# MB1296-USB_Antenna.net
KiCad netlist of a schematic drawn in Altium Designer
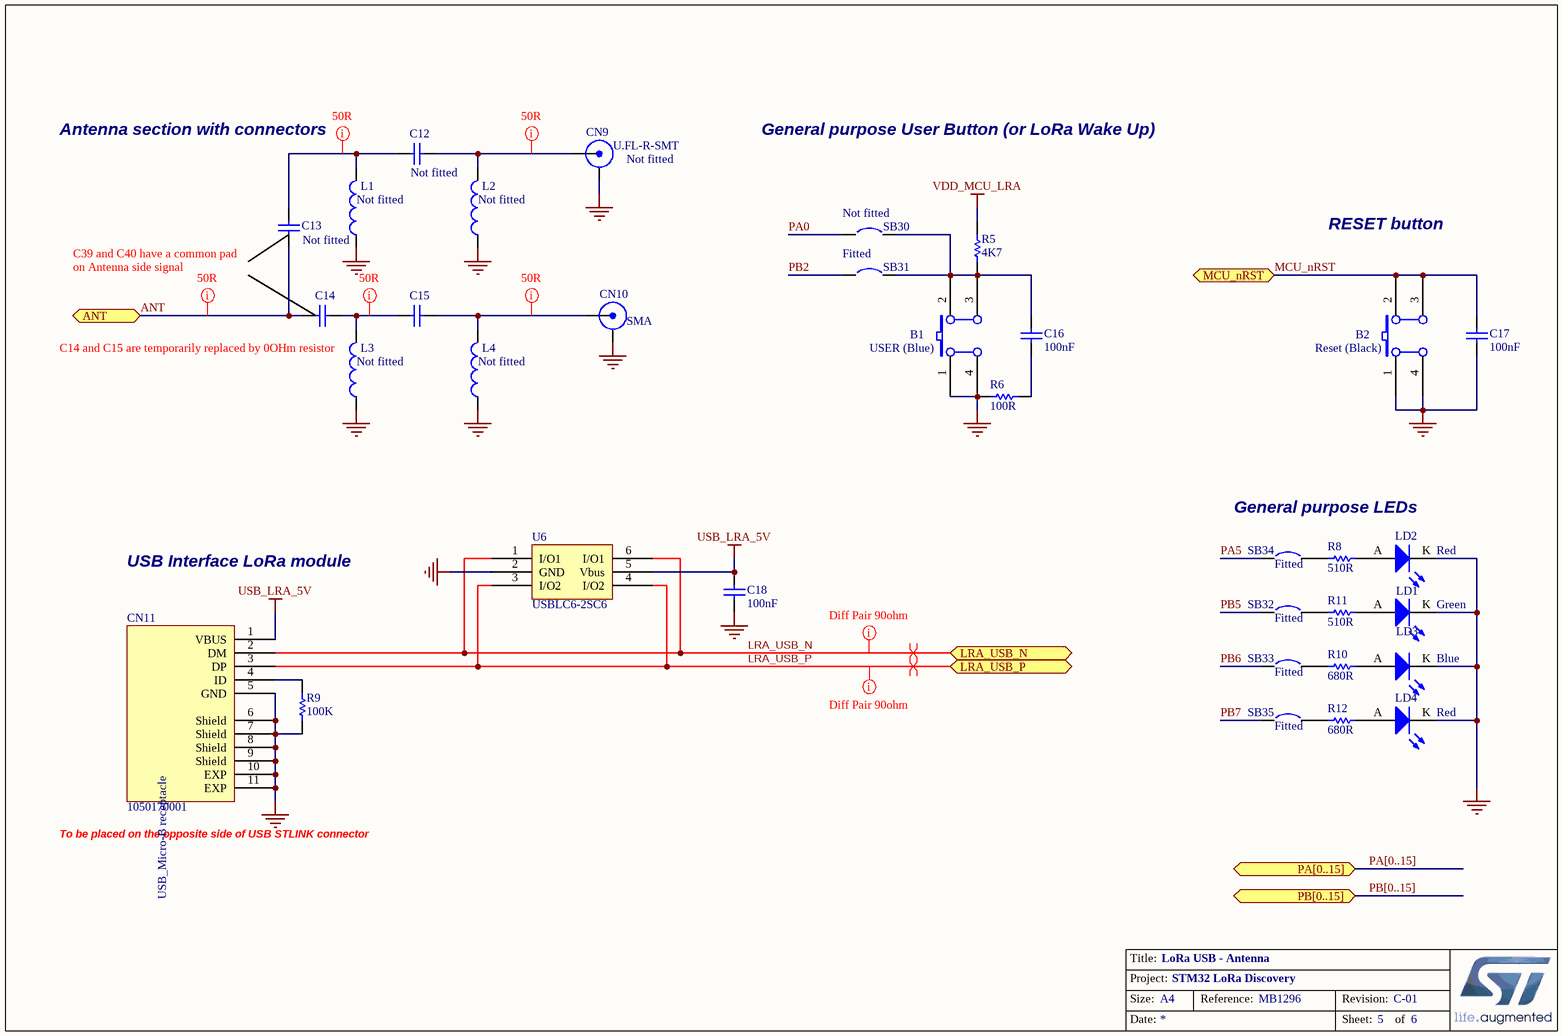
[diagram p0: MB1296-USB_Antenna.SchDoc]

(export (version "E")
  (design (tool "Eeschema 10.0.6"))
  (components
    (comp (ref "B1")
      (value "USER (Blue)")
      (footprint "PB10")
      (description "SE PUSHBUTTON")
      (fields (field (name "MANUFACTURER") "wealthmetal") (field (name "PROVIDED BY") "Subcon"))
      (libsource (lib "Documents") (part "SW PUSHBUTTON"))
    )
    (comp (ref "B2")
      (value "Reset (Black)")
      (footprint "PB10")
      (description "SE PUSHBUTTON")
      (fields (field (name "MANUFACTURER") "wealthmetal") (field (name "PROVIDED BY") "Subcon"))
      (libsource (lib "Documents") (part "SW PUSHBUTTON"))
    )
    (comp (ref "C12")
      (value "~")
      (footprint "0402")
      (description "0402")
      (libsource (lib "Capacitor_0402") (part "CAP SMD 0402 NPO 18PF 16V 5%"))
    )
    (comp (ref "C13")
      (value "~")
      (footprint "0402")
      (description "0402")
      (libsource (lib "Capacitor_0402") (part "CAP SMD 0402 NPO 18PF 16V 5%"))
    )
    (comp (ref "C14")
      (value "~")
      (footprint "0402")
      (description "0402")
      (libsource (lib "Capacitor_0402") (part "CAP SMD 0402 NPO 18PF 16V 5%"))
    )
    (comp (ref "C15")
      (value "~")
      (footprint "0402")
      (description "0402")
      (libsource (lib "Capacitor_0402") (part "CAP SMD 0402 NPO 18PF 16V 5%"))
    )
    (comp (ref "C16")
      (value "100nF")
      (footprint "0603C")
      (description "Capacitor 100nF")
      (fields (field (name "MANUFACTURER") "YAGEO") (field (name "PROVIDED BY") "Subcon"))
      (libsource (lib "MCD16-033-STM32_LRA_Eval_Board_1") (part "CAP"))
    )
    (comp (ref "C17")
      (value "100nF")
      (footprint "0603C")
      (description "Capacitor 100nF")
      (fields (field (name "MANUFACTURER") "YAGEO") (field (name "PROVIDED BY") "Subcon"))
      (libsource (lib "MCD16-033-STM32_LRA_Eval_Board_1") (part "CAP"))
    )
    (comp (ref "C18")
      (value "100nF")
      (footprint "0603C")
      (description "Capacitor 100nF")
      (fields (field (name "MANUFACTURER") "YAGEO") (field (name "PROVIDED BY") "Subcon"))
      (libsource (lib "MCD16-033-STM32_LRA_Eval_Board_1") (part "CAP"))
    )
    (comp (ref "CN9")
      (value "U.FL-R-SMT")
      (footprint "UFL-SMD")
      (libsource (lib "RF connector") (part "UFL"))
    )
    (comp (ref "CN10")
      (value "SMA")
      (footprint "SMA_COMBO_B")
      (libsource (lib "SCH_Lib_Phil_ST") (part "SMA"))
    )
    (comp (ref "CN11")
      (value "1050170001")
      (footprint "Molex_1050170001")
      (libsource (lib "Smartphone_accessory") (part "1050170001"))
    )
    (comp (ref "L1")
      (value "~")
      (footprint "0402")
      (libsource (lib "MCD16-033-STM32_LRA_Eval_Board_1") (part "BLM15HG102SN1D"))
    )
    (comp (ref "L2")
      (value "~")
      (footprint "0402")
      (libsource (lib "MCD16-033-STM32_LRA_Eval_Board_1") (part "BLM15HG102SN1D"))
    )
    (comp (ref "L3")
      (value "~")
      (footprint "0402")
      (libsource (lib "MCD16-033-STM32_LRA_Eval_Board_1") (part "BLM15HG102SN1D"))
    )
    (comp (ref "L4")
      (value "~")
      (footprint "0402")
      (libsource (lib "MCD16-033-STM32_LRA_Eval_Board_1") (part "BLM15HG102SN1D"))
    )
    (comp (ref "LD1")
      (value "Green")
      (footprint "0603D")
      (description "Typical RED, GREEN, YELLOW, AMBER GaAs LED")
      (fields (field (name "MANUFACTURER") "Everlight"))
      (libsource (lib "MB1296-STM32_LRA_Disco") (part "LED2"))
    )
    (comp (ref "LD2")
      (value "Red")
      (footprint "0603D")
      (description "Typical RED, GREEN, YELLOW, AMBER GaAs LED")
      (fields (field (name "MANUFACTURER") "Everlight"))
      (libsource (lib "MB1296-STM32_LRA_Disco") (part "LED2"))
    )
    (comp (ref "LD3")
      (value "Blue")
      (footprint "0603D")
      (description "Typical RED, GREEN, YELLOW, AMBER GaAs LED")
      (fields (field (name "MANUFACTURER") "Everlight"))
      (libsource (lib "MB1296-STM32_LRA_Disco") (part "LED2"))
    )
    (comp (ref "LD4")
      (value "Red")
      (footprint "0603D")
      (description "Typical RED, GREEN, YELLOW, AMBER GaAs LED")
      (fields (field (name "MANUFACTURER") "Everlight"))
      (libsource (lib "MB1296-STM32_LRA_Disco") (part "LED2"))
    )
    (comp (ref "R5")
      (value "4K7")
      (footprint "0603R")
      (description "Resistor")
      (fields (field (name "MANUFACTURER") "YAGEO") (field (name "PROVIDED BY") "Subcon"))
      (libsource (lib "MCD16-033-STM32_LRA_Eval_Board_1") (part "res1_4"))
    )
    (comp (ref "R6")
      (value "100R")
      (footprint "0603R")
      (description "Resistor")
      (fields (field (name "MANUFACTURER") "YAGEO") (field (name "PROVIDED BY") "Subcon"))
      (libsource (lib "MCD16-033-STM32_LRA_Eval_Board_1") (part "res1_4"))
    )
    (comp (ref "R8")
      (value "510R")
      (footprint "0603R")
      (description "Resistor")
      (fields (field (name "MANUFACTURER") "YAGEO") (field (name "PROVIDED BY") "Subcon"))
      (libsource (lib "MCD16-033-STM32_LRA_Eval_Board_1") (part "res1_4"))
    )
    (comp (ref "R9")
      (value "100K")
      (footprint "0603")
      (description "0603 100K 75V 5% 0.1W")
      (fields (field (name "MANUFACTURER") "YAGEO") (field (name "PROVIDED BY") "Subcon"))
      (libsource (lib "MCD16-033-STM32_LRA_Eval_Board_1") (part "RES SMD 0603 100K 75V 5% 0.1W"))
    )
    (comp (ref "R10")
      (value "680R")
      (footprint "0603R")
      (description "Resistor")
      (fields (field (name "MANUFACTURER") "YAGEO") (field (name "PROVIDED BY") "Subcon"))
      (libsource (lib "MCD16-033-STM32_LRA_Eval_Board_1") (part "res1_4"))
    )
    (comp (ref "R11")
      (value "510R")
      (footprint "0603R")
      (description "Resistor")
      (fields (field (name "MANUFACTURER") "YAGEO") (field (name "PROVIDED BY") "Subcon"))
      (libsource (lib "MCD16-033-STM32_LRA_Eval_Board_1") (part "res1_4"))
    )
    (comp (ref "R12")
      (value "680R")
      (footprint "0603R")
      (description "Resistor")
      (fields (field (name "MANUFACTURER") "YAGEO") (field (name "PROVIDED BY") "Subcon"))
      (libsource (lib "MCD16-033-STM32_LRA_Eval_Board_1") (part "res1_4"))
    )
    (comp (ref "SB30")
      (value "Circuit Breaker")
      (footprint "JP2_SMD")
      (libsource (lib "MCD16-033-STM32_LRA_Eval_Board_1") (part "Circuit Breaker"))
    )
    (comp (ref "SB31")
      (value "Circuit Breaker")
      (footprint "JP2_SMD")
      (libsource (lib "MCD16-033-STM32_LRA_Eval_Board_1") (part "Circuit Breaker"))
    )
    (comp (ref "SB32")
      (value "Circuit Breaker")
      (footprint "JP2_SMD")
      (libsource (lib "MCD16-033-STM32_LRA_Eval_Board_1") (part "Circuit Breaker"))
    )
    (comp (ref "SB33")
      (value "Circuit Breaker")
      (footprint "JP2_SMD")
      (libsource (lib "MCD16-033-STM32_LRA_Eval_Board_1") (part "Circuit Breaker"))
    )
    (comp (ref "SB34")
      (value "Circuit Breaker")
      (footprint "JP2_SMD")
      (libsource (lib "MCD16-033-STM32_LRA_Eval_Board_1") (part "Circuit Breaker"))
    )
    (comp (ref "SB35")
      (value "Circuit Breaker")
      (footprint "JP2_SMD")
      (libsource (lib "MCD16-033-STM32_LRA_Eval_Board_1") (part "Circuit Breaker"))
    )
    (comp (ref "U6")
      (value "USBLC6-2SC6")
      (footprint "SOT23-6L")
      (fields (field (name "MANUFACTURER") "STMicroelectronics") (field (name "PROVIDED BY") "STM"))
      (libsource (lib "MB1137") (part "USBLC6-2SC6"))
    )
  )
  (nets
    (net (code "27") (name "/ANT") (class "Default")
      (node (ref "C13") (pin "2") (pinfunction "2_2") (pintype "passive"))
      (node (ref "C14") (pin "1") (pinfunction "1_1") (pintype "passive"))
    )
    (net (code "28") (name "/LRA_USB_N") (class "Default")
      (node (ref "CN11") (pin "2") (pinfunction "DM_2") (pintype "passive"))
      (node (ref "U6") (pin "1") (pinfunction "I/O1_1") (pintype "passive"))
      (node (ref "U6") (pin "6") (pinfunction "I/O1_6") (pintype "passive"))
    )
    (net (code "29") (name "/LRA_USB_P") (class "Default")
      (node (ref "CN11") (pin "3") (pinfunction "DP_3") (pintype "passive"))
      (node (ref "U6") (pin "3") (pinfunction "I/O2_3") (pintype "passive"))
      (node (ref "U6") (pin "4") (pinfunction "I/O2_4") (pintype "passive"))
    )
    (net (code "30") (name "/MCU_nRST") (class "Default")
      (node (ref "B2") (pin "2") (pinfunction "B0_2") (pintype "passive"))
      (node (ref "B2") (pin "3") (pinfunction "B1_3") (pintype "passive"))
      (node (ref "C17") (pin "2") (pinfunction "2_2") (pintype "passive"))
    )
    (net (code "31") (name "/PA0") (class "Default")
      (node (ref "SB30") (pin "1") (pinfunction "1_1") (pintype "passive"))
    )
    (net (code "32") (name "/PA5") (class "Default")
      (node (ref "SB34") (pin "1") (pinfunction "1_1") (pintype "passive"))
    )
    (net (code "34") (name "/PB2") (class "Default")
      (node (ref "SB31") (pin "1") (pinfunction "1_1") (pintype "passive"))
    )
    (net (code "35") (name "/PB5") (class "Default")
      (node (ref "SB32") (pin "1") (pinfunction "1_1") (pintype "passive"))
    )
    (net (code "36") (name "/PB6") (class "Default")
      (node (ref "SB33") (pin "1") (pinfunction "1_1") (pintype "passive"))
    )
    (net (code "37") (name "/PB7") (class "Default")
      (node (ref "SB35") (pin "1") (pinfunction "1_1") (pintype "passive"))
    )
    (net (code "39") (name "GND") (class "Default")
      (node (ref "B1") (pin "1") (pinfunction "A0_1") (pintype "passive"))
      (node (ref "B1") (pin "4") (pinfunction "A1_4") (pintype "passive"))
      (node (ref "B2") (pin "1") (pinfunction "A0_1") (pintype "passive"))
      (node (ref "B2") (pin "4") (pinfunction "A1_4") (pintype "passive"))
      (node (ref "C17") (pin "1") (pinfunction "1_1") (pintype "passive"))
      (node (ref "C18") (pin "1") (pinfunction "1_1") (pintype "passive"))
      (node (ref "CN10") (pin "2") (pinfunction "Y_2") (pintype "passive"))
      (node (ref "CN11") (pin "10") (pinfunction "EXP_10") (pintype "passive"))
      (node (ref "CN11") (pin "11") (pinfunction "EXP_11") (pintype "passive"))
      (node (ref "CN11") (pin "5") (pinfunction "GND_5") (pintype "passive"))
      (node (ref "CN11") (pin "6") (pinfunction "Shield_6") (pintype "passive"))
      (node (ref "CN11") (pin "7") (pinfunction "Shield_7") (pintype "passive"))
      (node (ref "CN11") (pin "8") (pinfunction "Shield_8") (pintype "passive"))
      (node (ref "CN11") (pin "9") (pinfunction "Shield_9") (pintype "passive"))
      (node (ref "CN9") (pin "2") (pinfunction "Y_2") (pintype "passive"))
      (node (ref "L1") (pin "1") (pinfunction "1_1") (pintype "passive"))
      (node (ref "L2") (pin "1") (pinfunction "1_1") (pintype "passive"))
      (node (ref "L3") (pin "1") (pinfunction "1_1") (pintype "passive"))
      (node (ref "L4") (pin "1") (pinfunction "1_1") (pintype "passive"))
      (node (ref "LD1") (pin "K") (pinfunction "K_K") (pintype "passive"))
      (node (ref "LD2") (pin "K") (pinfunction "K_K") (pintype "passive"))
      (node (ref "LD3") (pin "K") (pinfunction "K_K") (pintype "passive"))
      (node (ref "LD4") (pin "K") (pinfunction "K_K") (pintype "passive"))
      (node (ref "R6") (pin "2") (pinfunction "2_2") (pintype "passive"))
      (node (ref "R9") (pin "1") (pinfunction "1_1") (pintype "passive"))
      (node (ref "U6") (pin "2") (pinfunction "GND_2") (pintype "passive"))
    )
    (net (code "40") (name "Net-(B1-B0)") (class "Default")
      (node (ref "B1") (pin "2") (pinfunction "B0_2") (pintype "passive"))
      (node (ref "B1") (pin "3") (pinfunction "B1_3") (pintype "passive"))
      (node (ref "C16") (pin "2") (pinfunction "2_2") (pintype "passive"))
      (node (ref "R5") (pin "1") (pinfunction "1_1") (pintype "passive"))
      (node (ref "SB30") (pin "2") (pinfunction "2_2") (pintype "passive"))
      (node (ref "SB31") (pin "2") (pinfunction "2_2") (pintype "passive"))
    )
    (net (code "41") (name "Net-(C12-Pad1)") (class "Default")
      (node (ref "C12") (pin "1") (pinfunction "1_1") (pintype "passive"))
      (node (ref "C13") (pin "1") (pinfunction "1_1") (pintype "passive"))
      (node (ref "L1") (pin "2") (pinfunction "2_2") (pintype "passive"))
    )
    (net (code "42") (name "Net-(C14-Pad2)") (class "Default")
      (node (ref "C14") (pin "2") (pinfunction "2_2") (pintype "passive"))
      (node (ref "C15") (pin "1") (pinfunction "1_1") (pintype "passive"))
      (node (ref "L3") (pin "2") (pinfunction "2_2") (pintype "passive"))
    )
    (net (code "43") (name "Net-(C16-Pad1)") (class "Default")
      (node (ref "C16") (pin "1") (pinfunction "1_1") (pintype "passive"))
      (node (ref "R6") (pin "1") (pinfunction "1_1") (pintype "passive"))
    )
    (net (code "44") (name "Net-(CN9-X)") (class "Default")
      (node (ref "C12") (pin "2") (pinfunction "2_2") (pintype "passive"))
      (node (ref "CN9") (pin "1") (pinfunction "X_1") (pintype "passive"))
      (node (ref "L2") (pin "2") (pinfunction "2_2") (pintype "passive"))
    )
    (net (code "45") (name "Net-(CN10-X)") (class "Default")
      (node (ref "C15") (pin "2") (pinfunction "2_2") (pintype "passive"))
      (node (ref "CN10") (pin "1") (pinfunction "X_1") (pintype "passive"))
      (node (ref "L4") (pin "2") (pinfunction "2_2") (pintype "passive"))
    )
    (net (code "46") (name "Net-(CN11-ID)") (class "Default")
      (node (ref "CN11") (pin "4") (pinfunction "ID_4") (pintype "passive"))
      (node (ref "R9") (pin "2") (pinfunction "2_2") (pintype "passive"))
    )
    (net (code "47") (name "Net-(LD1-PadA)") (class "Default")
      (node (ref "LD1") (pin "A") (pinfunction "A_A") (pintype "passive"))
      (node (ref "R11") (pin "2") (pinfunction "2_2") (pintype "passive"))
    )
    (net (code "48") (name "Net-(LD2-PadA)") (class "Default")
      (node (ref "LD2") (pin "A") (pinfunction "A_A") (pintype "passive"))
      (node (ref "R8") (pin "2") (pinfunction "2_2") (pintype "passive"))
    )
    (net (code "49") (name "Net-(LD3-PadA)") (class "Default")
      (node (ref "LD3") (pin "A") (pinfunction "A_A") (pintype "passive"))
      (node (ref "R10") (pin "2") (pinfunction "2_2") (pintype "passive"))
    )
    (net (code "50") (name "Net-(LD4-PadA)") (class "Default")
      (node (ref "LD4") (pin "A") (pinfunction "A_A") (pintype "passive"))
      (node (ref "R12") (pin "2") (pinfunction "2_2") (pintype "passive"))
    )
    (net (code "51") (name "Net-(R8-Pad1)") (class "Default")
      (node (ref "R8") (pin "1") (pinfunction "1_1") (pintype "passive"))
      (node (ref "SB34") (pin "2") (pinfunction "2_2") (pintype "passive"))
    )
    (net (code "52") (name "Net-(R10-Pad1)") (class "Default")
      (node (ref "R10") (pin "1") (pinfunction "1_1") (pintype "passive"))
      (node (ref "SB33") (pin "2") (pinfunction "2_2") (pintype "passive"))
    )
    (net (code "53") (name "Net-(R11-Pad1)") (class "Default")
      (node (ref "R11") (pin "1") (pinfunction "1_1") (pintype "passive"))
      (node (ref "SB32") (pin "2") (pinfunction "2_2") (pintype "passive"))
    )
    (net (code "54") (name "Net-(R12-Pad1)") (class "Default")
      (node (ref "R12") (pin "1") (pinfunction "1_1") (pintype "passive"))
      (node (ref "SB35") (pin "2") (pinfunction "2_2") (pintype "passive"))
    )
    (net (code "55") (name "USB_LRA_5V") (class "Default")
      (node (ref "C18") (pin "2") (pinfunction "2_2") (pintype "passive"))
      (node (ref "CN11") (pin "1") (pinfunction "VBUS_1") (pintype "passive"))
      (node (ref "U6") (pin "5") (pinfunction "Vbus_5") (pintype "passive"))
    )
    (net (code "56") (name "VDD_MCU_LRA") (class "Default")
      (node (ref "R5") (pin "2") (pinfunction "2_2") (pintype "passive"))
    )
  )
)
